# Light_TO220.net
KiCad netlist of a schematic drawn in EAGLE
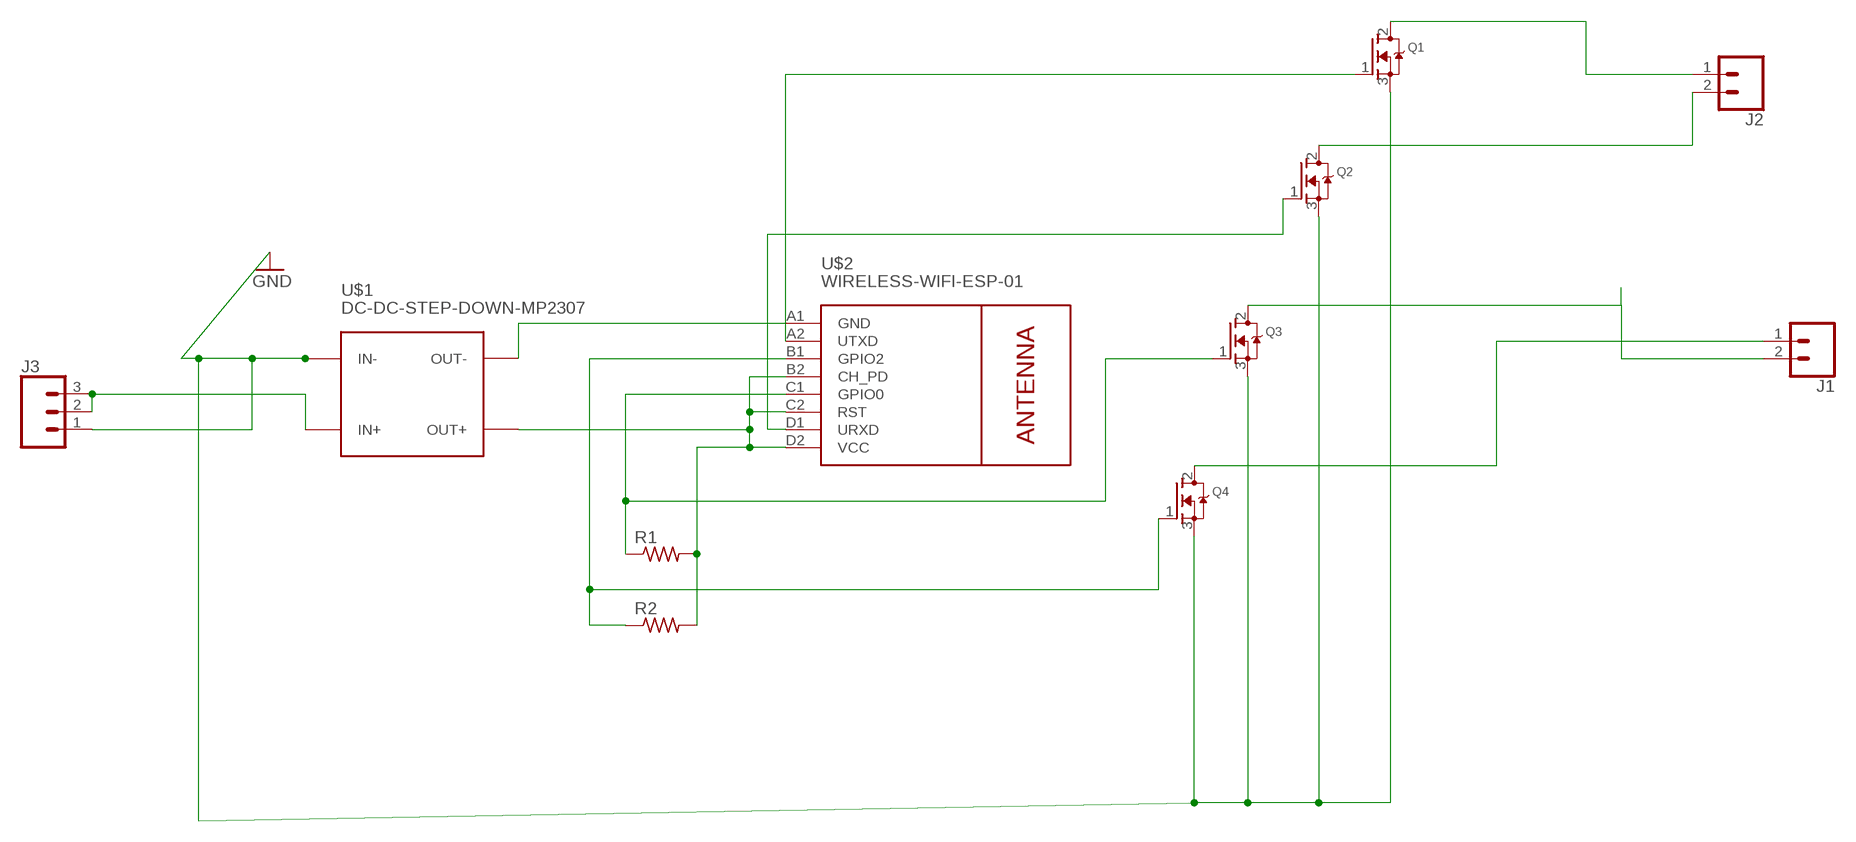
[diagram p0: schematic, sheet 1]

(export (version "E")
  (design (tool "Eeschema 10.0.6"))
  (components
    (comp (ref "J1")
      (value "CONN_023.5MM")
      (footprint "eagle-import:SCREWTERMINAL-3.5MM-2")
      (libsource (lib "eagle-import") (part "CONN_023.5MM"))
    )
    (comp (ref "J2")
      (value "CONN_023.5MM")
      (footprint "eagle-import:SCREWTERMINAL-3.5MM-2")
      (libsource (lib "eagle-import") (part "CONN_023.5MM"))
    )
    (comp (ref "J3")
      (value "CONN_03SCREW")
      (footprint "eagle-import:SCREWTERMINAL-3.5MM-3")
      (libsource (lib "eagle-import") (part "CONN_03SCREW"))
    )
    (comp (ref "Q1")
      (value "MOSFET-NGDS_TO220V")
      (footprint "eagle-import:TO220V")
      (libsource (lib "eagle-import") (part "MOSFET-NGDS_TO220V"))
    )
    (comp (ref "Q2")
      (value "MOSFET-NGDS_TO220V")
      (footprint "eagle-import:TO220V")
      (libsource (lib "eagle-import") (part "MOSFET-NGDS_TO220V"))
    )
    (comp (ref "Q3")
      (value "MOSFET-NGDS_TO220V")
      (footprint "eagle-import:TO220V")
      (libsource (lib "eagle-import") (part "MOSFET-NGDS_TO220V"))
    )
    (comp (ref "Q4")
      (value "MOSFET-NGDS_TO220V")
      (footprint "eagle-import:TO220V")
      (libsource (lib "eagle-import") (part "MOSFET-NGDS_TO220V"))
    )
    (comp (ref "R1")
      (value "R-US_R0805")
      (footprint "eagle-import:R0805")
      (libsource (lib "eagle-import") (part "R-US_R0805"))
    )
    (comp (ref "R2")
      (value "R-US_R0805")
      (footprint "eagle-import:R0805")
      (libsource (lib "eagle-import") (part "R-US_R0805"))
    )
    (comp (ref "U$1")
      (value "DC-DC-STEP-DOWN-MP2307")
      (footprint "eagle-import:DC-DC-STEP-DOWN-MP2307")
      (libsource (lib "eagle-import") (part "DC-DC-STEP-DOWN-MP2307"))
    )
    (comp (ref "U$2")
      (value "WIRELESS-WIFI-ESP-01")
      (footprint "eagle-import:WIRELESS-WIFI-ESP-01")
      (fields (field (name "SPICEPREFIX") "X"))
      (libsource (lib "eagle-import") (part "WIRELESS-WIFI-ESP-01"))
    )
  )
  (nets
    (net (code "1") (name "GND") (class "Default")
      (node (ref "J3") (pin "1") (pinfunction "1_1") (pintype "passive"))
      (node (ref "Q1") (pin "3") (pinfunction "S_3") (pintype "bidirectional"))
      (node (ref "Q2") (pin "3") (pinfunction "S_3") (pintype "bidirectional"))
      (node (ref "Q3") (pin "3") (pinfunction "S_3") (pintype "bidirectional"))
      (node (ref "Q4") (pin "3") (pinfunction "S_3") (pintype "bidirectional"))
      (node (ref "U$1") (pin "IN-") (pinfunction "IN-_IN-") (pintype "bidirectional"))
    )
    (net (code "2") (name "Net-(J3-Pad2)") (class "Default")
      (node (ref "J3") (pin "2") (pinfunction "2_2") (pintype "passive"))
      (node (ref "J3") (pin "3") (pinfunction "3_3") (pintype "passive"))
      (node (ref "U$1") (pin "IN+") (pinfunction "IN+_IN+") (pintype "bidirectional"))
    )
    (net (code "3") (name "Net-(Q1-D)") (class "Default")
      (node (ref "J2") (pin "1") (pinfunction "1_1") (pintype "passive"))
      (node (ref "Q1") (pin "2") (pinfunction "D_2") (pintype "bidirectional"))
    )
    (net (code "4") (name "Net-(Q1-G)") (class "Default")
      (node (ref "Q1") (pin "1") (pinfunction "G_1") (pintype "bidirectional"))
      (node (ref "U$2") (pin "A2") (pinfunction "UTXD_A2") (pintype "bidirectional"))
    )
    (net (code "5") (name "Net-(Q2-D)") (class "Default")
      (node (ref "J2") (pin "2") (pinfunction "2_2") (pintype "passive"))
      (node (ref "Q2") (pin "2") (pinfunction "D_2") (pintype "bidirectional"))
    )
    (net (code "6") (name "Net-(Q2-G)") (class "Default")
      (node (ref "Q2") (pin "1") (pinfunction "G_1") (pintype "bidirectional"))
      (node (ref "U$2") (pin "D1") (pinfunction "URXD_D1") (pintype "bidirectional"))
    )
    (net (code "7") (name "Net-(Q3-D)") (class "Default")
      (node (ref "J1") (pin "2") (pinfunction "2_2") (pintype "passive"))
      (node (ref "Q3") (pin "2") (pinfunction "D_2") (pintype "bidirectional"))
    )
    (net (code "8") (name "Net-(Q3-G)") (class "Default")
      (node (ref "Q3") (pin "1") (pinfunction "G_1") (pintype "bidirectional"))
      (node (ref "R1") (pin "1") (pinfunction "1_1") (pintype "passive"))
      (node (ref "U$2") (pin "C1") (pinfunction "GPIO0_C1") (pintype "bidirectional"))
    )
    (net (code "9") (name "Net-(Q4-D)") (class "Default")
      (node (ref "J1") (pin "1") (pinfunction "1_1") (pintype "passive"))
      (node (ref "Q4") (pin "2") (pinfunction "D_2") (pintype "bidirectional"))
    )
    (net (code "10") (name "Net-(Q4-G)") (class "Default")
      (node (ref "Q4") (pin "1") (pinfunction "G_1") (pintype "bidirectional"))
      (node (ref "R2") (pin "1") (pinfunction "1_1") (pintype "passive"))
      (node (ref "U$2") (pin "B1") (pinfunction "GPIO2_B1") (pintype "bidirectional"))
    )
    (net (code "11") (name "Net-(U$2-CH_PD)") (class "Default")
      (node (ref "R1") (pin "2") (pinfunction "2_2") (pintype "passive"))
      (node (ref "R2") (pin "2") (pinfunction "2_2") (pintype "passive"))
      (node (ref "U$1") (pin "OUT+") (pinfunction "OUT+_OUT+") (pintype "bidirectional"))
      (node (ref "U$2") (pin "B2") (pinfunction "CH_PD_B2") (pintype "bidirectional"))
      (node (ref "U$2") (pin "C2") (pinfunction "RST_C2") (pintype "bidirectional"))
      (node (ref "U$2") (pin "D2") (pinfunction "VCC_D2") (pintype "power_in"))
    )
    (net (code "12") (name "Net-(U$2-GND)") (class "Default")
      (node (ref "U$1") (pin "OUT-") (pinfunction "OUT-_OUT-") (pintype "bidirectional"))
      (node (ref "U$2") (pin "A1") (pinfunction "GND_A1") (pintype "power_in"))
    )
  )
)
